# ver061_LPF.net
KiCad netlist of a schematic drawn in Altium Designer
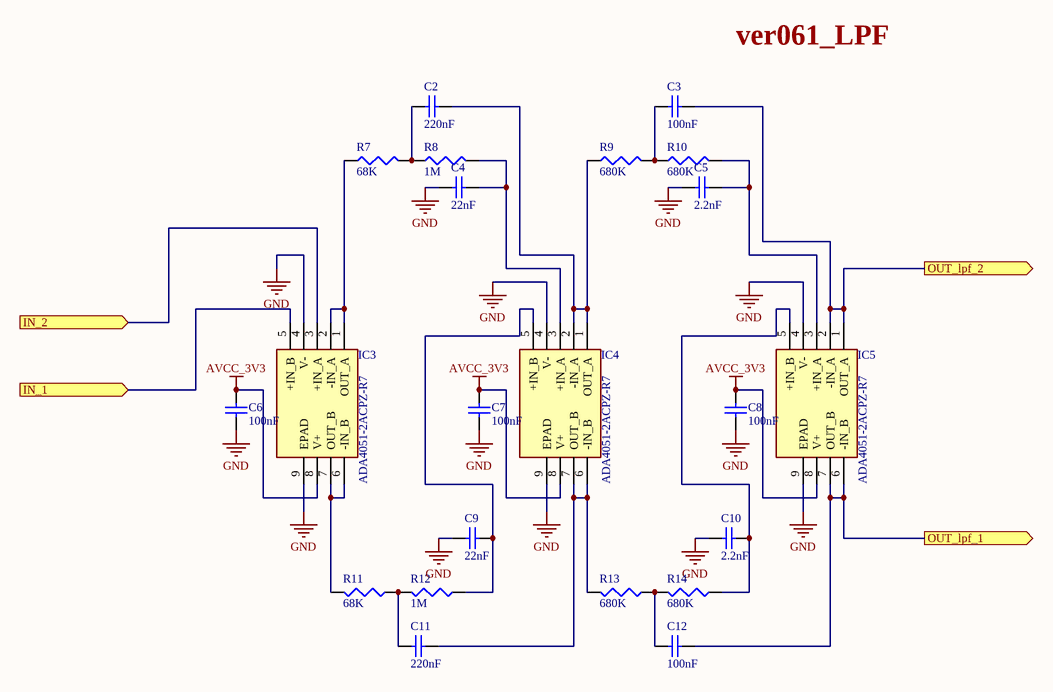
[diagram p0: ver061_LPF.SchDoc]

(export (version "E")
  (design (tool "Eeschema 10.0.6"))
  (components
    (comp (ref "C2")
      (value "220nF")
      (footprint "0402")
      (description "Capacitor (Semiconductor SIM Model)")
      (fields (field (name "Comment") "Cap Semi") (field (name "PUBLISHER") "Altium Limited"))
      (libsource (lib "Miscellaneous Devices") (part "Cap Semi"))
    )
    (comp (ref "C3")
      (value "100nF")
      (footprint "0402")
      (description "Capacitor (Semiconductor SIM Model)")
      (fields (field (name "Comment") "Cap Semi") (field (name "PUBLISHER") "Altium Limited"))
      (libsource (lib "Miscellaneous Devices") (part "Cap Semi"))
    )
    (comp (ref "C4")
      (value "22nF")
      (footprint "0402")
      (description "Capacitor (Semiconductor SIM Model)")
      (fields (field (name "Comment") "Cap Semi") (field (name "PUBLISHER") "Altium Limited"))
      (libsource (lib "Miscellaneous Devices") (part "Cap Semi"))
    )
    (comp (ref "C5")
      (value "2.2nF")
      (footprint "0402")
      (description "Capacitor (Semiconductor SIM Model)")
      (fields (field (name "Comment") "Cap Semi") (field (name "PUBLISHER") "Altium Limited"))
      (libsource (lib "Miscellaneous Devices") (part "Cap Semi"))
    )
    (comp (ref "C6")
      (value "100nF")
      (footprint "1608[0603]")
      (description "Capacitor (Semiconductor SIM Model)")
      (fields (field (name "Comment") "Cap Semi") (field (name "PUBLISHER") "Altium Limited"))
      (libsource (lib "Miscellaneous Devices") (part "Cap Semi"))
    )
    (comp (ref "C7")
      (value "100nF")
      (footprint "1608[0603]")
      (description "Capacitor (Semiconductor SIM Model)")
      (fields (field (name "Comment") "Cap Semi") (field (name "PUBLISHER") "Altium Limited"))
      (libsource (lib "Miscellaneous Devices") (part "Cap Semi"))
    )
    (comp (ref "C8")
      (value "100nF")
      (footprint "1608[0603]")
      (description "Capacitor (Semiconductor SIM Model)")
      (fields (field (name "Comment") "Cap Semi") (field (name "PUBLISHER") "Altium Limited"))
      (libsource (lib "Miscellaneous Devices") (part "Cap Semi"))
    )
    (comp (ref "C9")
      (value "22nF")
      (footprint "0402")
      (description "Capacitor (Semiconductor SIM Model)")
      (fields (field (name "Comment") "Cap Semi") (field (name "PUBLISHER") "Altium Limited"))
      (libsource (lib "Miscellaneous Devices") (part "Cap Semi"))
    )
    (comp (ref "C10")
      (value "2.2nF")
      (footprint "0402")
      (description "Capacitor (Semiconductor SIM Model)")
      (fields (field (name "Comment") "Cap Semi") (field (name "PUBLISHER") "Altium Limited"))
      (libsource (lib "Miscellaneous Devices") (part "Cap Semi"))
    )
    (comp (ref "C11")
      (value "220nF")
      (footprint "0402")
      (description "Capacitor (Semiconductor SIM Model)")
      (fields (field (name "Comment") "Cap Semi") (field (name "PUBLISHER") "Altium Limited"))
      (libsource (lib "Miscellaneous Devices") (part "Cap Semi"))
    )
    (comp (ref "C12")
      (value "100nF")
      (footprint "0402")
      (description "Capacitor (Semiconductor SIM Model)")
      (fields (field (name "Comment") "Cap Semi") (field (name "PUBLISHER") "Altium Limited"))
      (libsource (lib "Miscellaneous Devices") (part "Cap Semi"))
    )
    (comp (ref "IC3")
      (value "ADA4051-2ACPZ-R7")
      (footprint "DFN300X300X90-9N")
      (description "Integrated Circuit")
      (fields (field (name "MOUSER PART NUMBER") "584-ADA4051-2ACPZ-R7"))
      (libsource (lib "nanowire") (part "ADA4051-2ACPZ-R7"))
    )
    (comp (ref "IC4")
      (value "ADA4051-2ACPZ-R7")
      (footprint "DFN300X300X90-9N")
      (description "Integrated Circuit")
      (fields (field (name "MOUSER PART NUMBER") "584-ADA4051-2ACPZ-R7"))
      (libsource (lib "nanowire") (part "ADA4051-2ACPZ-R7"))
    )
    (comp (ref "IC5")
      (value "ADA4051-2ACPZ-R7")
      (footprint "DFN300X300X90-9N")
      (description "Integrated Circuit")
      (fields (field (name "MOUSER PART NUMBER") "584-ADA4051-2ACPZ-R7"))
      (libsource (lib "nanowire") (part "ADA4051-2ACPZ-R7"))
    )
    (comp (ref "R7")
      (value "68K")
      (footprint "RESC1005X35N")
      (description "Resistor")
      (fields (field (name "Comment") "Res3") (field (name "PUBLISHER") "Altium Limited"))
      (libsource (lib "Miscellaneous Devices") (part "Res3"))
    )
    (comp (ref "R8")
      (value "1M")
      (footprint "RESC1005X35N")
      (description "Resistor")
      (fields (field (name "Comment") "Res3") (field (name "PUBLISHER") "Altium Limited"))
      (libsource (lib "Miscellaneous Devices") (part "Res3"))
    )
    (comp (ref "R9")
      (value "680K")
      (footprint "RESC1005X35N")
      (description "Resistor")
      (fields (field (name "Comment") "Res3") (field (name "PUBLISHER") "Altium Limited"))
      (libsource (lib "Miscellaneous Devices") (part "Res3"))
    )
    (comp (ref "R10")
      (value "680K")
      (footprint "RESC1005X35N")
      (description "Resistor")
      (fields (field (name "Comment") "Res3") (field (name "PUBLISHER") "Altium Limited"))
      (libsource (lib "Miscellaneous Devices") (part "Res3"))
    )
    (comp (ref "R11")
      (value "68K")
      (footprint "RESC1005X35N")
      (description "Resistor")
      (fields (field (name "Comment") "Res3") (field (name "PUBLISHER") "Altium Limited"))
      (libsource (lib "Miscellaneous Devices") (part "Res3"))
    )
    (comp (ref "R12")
      (value "1M")
      (footprint "RESC1005X35N")
      (description "Resistor")
      (fields (field (name "Comment") "Res3") (field (name "PUBLISHER") "Altium Limited"))
      (libsource (lib "Miscellaneous Devices") (part "Res3"))
    )
    (comp (ref "R13")
      (value "680K")
      (footprint "RESC1005X35N")
      (description "Resistor")
      (fields (field (name "Comment") "Res3") (field (name "PUBLISHER") "Altium Limited"))
      (libsource (lib "Miscellaneous Devices") (part "Res3"))
    )
    (comp (ref "R14")
      (value "680K")
      (footprint "RESC1005X35N")
      (description "Resistor")
      (fields (field (name "Comment") "Res3") (field (name "PUBLISHER") "Altium Limited"))
      (libsource (lib "Miscellaneous Devices") (part "Res3"))
    )
  )
  (nets
    (net (code "1") (name "/IN_1") (class "Default")
      (node (ref "IC3") (pin "5") (pinfunction "+IN_B_5") (pintype "passive"))
    )
    (net (code "2") (name "/IN_2") (class "Default")
      (node (ref "IC3") (pin "3") (pinfunction "+IN_A_3") (pintype "passive"))
    )
    (net (code "3") (name "/OUT_lpf_1") (class "Default")
      (node (ref "C12") (pin "2") (pinfunction "2_2") (pintype "passive"))
      (node (ref "IC5") (pin "6") (pinfunction "-IN_B_6") (pintype "passive"))
      (node (ref "IC5") (pin "7") (pinfunction "OUT_B_7") (pintype "passive"))
    )
    (net (code "4") (name "/OUT_lpf_2") (class "Default")
      (node (ref "C3") (pin "2") (pinfunction "2_2") (pintype "passive"))
      (node (ref "IC5") (pin "1") (pinfunction "OUT_A_1") (pintype "passive"))
      (node (ref "IC5") (pin "2") (pinfunction "-IN_A_2") (pintype "passive"))
    )
    (net (code "5") (name "AVCC_3V3") (class "Default")
      (node (ref "C6") (pin "2") (pinfunction "2_2") (pintype "passive"))
      (node (ref "C7") (pin "2") (pinfunction "2_2") (pintype "passive"))
      (node (ref "C8") (pin "2") (pinfunction "2_2") (pintype "passive"))
      (node (ref "IC3") (pin "8") (pinfunction "V+_8") (pintype "passive"))
      (node (ref "IC4") (pin "8") (pinfunction "V+_8") (pintype "passive"))
      (node (ref "IC5") (pin "8") (pinfunction "V+_8") (pintype "passive"))
    )
    (net (code "6") (name "GND") (class "Default")
      (node (ref "C10") (pin "1") (pinfunction "1_1") (pintype "passive"))
      (node (ref "C4") (pin "1") (pinfunction "1_1") (pintype "passive"))
      (node (ref "C5") (pin "1") (pinfunction "1_1") (pintype "passive"))
      (node (ref "C6") (pin "1") (pinfunction "1_1") (pintype "passive"))
      (node (ref "C7") (pin "1") (pinfunction "1_1") (pintype "passive"))
      (node (ref "C8") (pin "1") (pinfunction "1_1") (pintype "passive"))
      (node (ref "C9") (pin "1") (pinfunction "1_1") (pintype "passive"))
      (node (ref "IC3") (pin "4") (pinfunction "V-_4") (pintype "passive"))
      (node (ref "IC3") (pin "9") (pinfunction "EPAD_9") (pintype "passive"))
      (node (ref "IC4") (pin "4") (pinfunction "V-_4") (pintype "passive"))
      (node (ref "IC4") (pin "9") (pinfunction "EPAD_9") (pintype "passive"))
      (node (ref "IC5") (pin "4") (pinfunction "V-_4") (pintype "passive"))
      (node (ref "IC5") (pin "9") (pinfunction "EPAD_9") (pintype "passive"))
    )
    (net (code "7") (name "Net-(C2-Pad1)") (class "Default")
      (node (ref "C2") (pin "1") (pinfunction "1_1") (pintype "passive"))
      (node (ref "R7") (pin "1") (pinfunction "1_1") (pintype "passive"))
      (node (ref "R8") (pin "2") (pinfunction "2_2") (pintype "passive"))
    )
    (net (code "8") (name "Net-(C3-Pad1)") (class "Default")
      (node (ref "C3") (pin "1") (pinfunction "1_1") (pintype "passive"))
      (node (ref "R10") (pin "2") (pinfunction "2_2") (pintype "passive"))
      (node (ref "R9") (pin "1") (pinfunction "1_1") (pintype "passive"))
    )
    (net (code "9") (name "Net-(C11-Pad1)") (class "Default")
      (node (ref "C11") (pin "1") (pinfunction "1_1") (pintype "passive"))
      (node (ref "R11") (pin "1") (pinfunction "1_1") (pintype "passive"))
      (node (ref "R12") (pin "2") (pinfunction "2_2") (pintype "passive"))
    )
    (net (code "10") (name "Net-(C12-Pad1)") (class "Default")
      (node (ref "C12") (pin "1") (pinfunction "1_1") (pintype "passive"))
      (node (ref "R13") (pin "1") (pinfunction "1_1") (pintype "passive"))
      (node (ref "R14") (pin "2") (pinfunction "2_2") (pintype "passive"))
    )
    (net (code "11") (name "Net-(IC3--IN_A)") (class "Default")
      (node (ref "IC3") (pin "1") (pinfunction "OUT_A_1") (pintype "passive"))
      (node (ref "IC3") (pin "2") (pinfunction "-IN_A_2") (pintype "passive"))
      (node (ref "R7") (pin "2") (pinfunction "2_2") (pintype "passive"))
    )
    (net (code "12") (name "Net-(IC3--IN_B)") (class "Default")
      (node (ref "IC3") (pin "6") (pinfunction "-IN_B_6") (pintype "passive"))
      (node (ref "IC3") (pin "7") (pinfunction "OUT_B_7") (pintype "passive"))
      (node (ref "R11") (pin "2") (pinfunction "2_2") (pintype "passive"))
    )
    (net (code "13") (name "Net-(IC4-+IN_A)") (class "Default")
      (node (ref "C4") (pin "2") (pinfunction "2_2") (pintype "passive"))
      (node (ref "IC4") (pin "3") (pinfunction "+IN_A_3") (pintype "passive"))
      (node (ref "R8") (pin "1") (pinfunction "1_1") (pintype "passive"))
    )
    (net (code "14") (name "Net-(IC4-+IN_B)") (class "Default")
      (node (ref "C9") (pin "2") (pinfunction "2_2") (pintype "passive"))
      (node (ref "IC4") (pin "5") (pinfunction "+IN_B_5") (pintype "passive"))
      (node (ref "R12") (pin "1") (pinfunction "1_1") (pintype "passive"))
    )
    (net (code "15") (name "Net-(IC4--IN_A)") (class "Default")
      (node (ref "C2") (pin "2") (pinfunction "2_2") (pintype "passive"))
      (node (ref "IC4") (pin "1") (pinfunction "OUT_A_1") (pintype "passive"))
      (node (ref "IC4") (pin "2") (pinfunction "-IN_A_2") (pintype "passive"))
      (node (ref "R9") (pin "2") (pinfunction "2_2") (pintype "passive"))
    )
    (net (code "16") (name "Net-(IC4--IN_B)") (class "Default")
      (node (ref "C11") (pin "2") (pinfunction "2_2") (pintype "passive"))
      (node (ref "IC4") (pin "6") (pinfunction "-IN_B_6") (pintype "passive"))
      (node (ref "IC4") (pin "7") (pinfunction "OUT_B_7") (pintype "passive"))
      (node (ref "R13") (pin "2") (pinfunction "2_2") (pintype "passive"))
    )
    (net (code "17") (name "Net-(IC5-+IN_A)") (class "Default")
      (node (ref "C5") (pin "2") (pinfunction "2_2") (pintype "passive"))
      (node (ref "IC5") (pin "3") (pinfunction "+IN_A_3") (pintype "passive"))
      (node (ref "R10") (pin "1") (pinfunction "1_1") (pintype "passive"))
    )
    (net (code "18") (name "Net-(IC5-+IN_B)") (class "Default")
      (node (ref "C10") (pin "2") (pinfunction "2_2") (pintype "passive"))
      (node (ref "IC5") (pin "5") (pinfunction "+IN_B_5") (pintype "passive"))
      (node (ref "R14") (pin "1") (pinfunction "1_1") (pintype "passive"))
    )
  )
)
